# Acceleration_module.net
KiCad netlist of a schematic drawn in Altium Designer
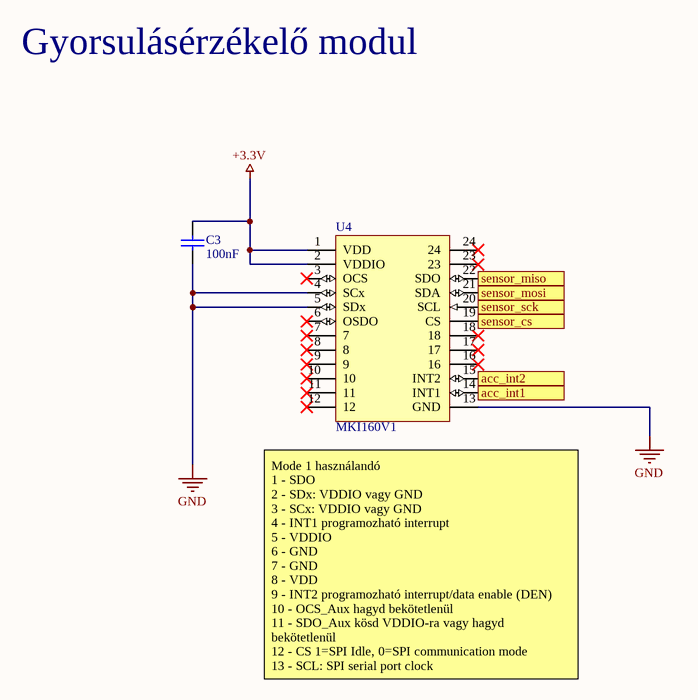
[diagram p0: Acceleration_module.SchDoc]

(export (version "E")
  (design (tool "Eeschema 10.0.6"))
  (components
    (comp (ref "C3")
      (value "100nF")
      (footprint "FP_1206_CAP_125")
      (description "Capacitor")
      (fields (field (name "TOLERANCE") "10%") (field (name "VOLTAGE") "50V"))
      (libsource (lib "hallglib") (part "CAP"))
    )
    (comp (ref "U4")
      (value "MKI160V1")
      (footprint "FP_DIL24")
      (description "LSM6DS3 inertial module adapter")
      (libsource (lib "hallglib") (part "MKI160V1"))
    )
  )
  (nets
    (net (code "1") (name "+3.3V") (class "Default")
      (node (ref "C3") (pin "2") (pinfunction "2_2") (pintype "passive"))
      (node (ref "U4") (pin "1") (pinfunction "VDD_1") (pintype "power_in"))
      (node (ref "U4") (pin "2") (pinfunction "VDDIO_2") (pintype "power_in"))
    )
    (net (code "2") (name "/acc_int1") (class "Default")
      (node (ref "U4") (pin "14") (pinfunction "INT1_14") (pintype "bidirectional"))
    )
    (net (code "3") (name "/acc_int2") (class "Default")
      (node (ref "U4") (pin "15") (pinfunction "INT2_15") (pintype "bidirectional"))
    )
    (net (code "4") (name "/sensor_cs") (class "Default")
      (node (ref "U4") (pin "19") (pinfunction "CS_19") (pintype "passive"))
    )
    (net (code "5") (name "/sensor_miso") (class "Default")
      (node (ref "U4") (pin "22") (pinfunction "SDO_22") (pintype "bidirectional"))
    )
    (net (code "6") (name "/sensor_mosi") (class "Default")
      (node (ref "U4") (pin "21") (pinfunction "SDA_21") (pintype "bidirectional"))
    )
    (net (code "7") (name "/sensor_sck") (class "Default")
      (node (ref "U4") (pin "20") (pinfunction "SCL_20") (pintype "input"))
    )
    (net (code "8") (name "GND") (class "Default")
      (node (ref "C3") (pin "1") (pinfunction "1_1") (pintype "passive"))
      (node (ref "U4") (pin "13") (pinfunction "GND_13") (pintype "power_in"))
      (node (ref "U4") (pin "4") (pinfunction "SCx_4") (pintype "bidirectional"))
      (node (ref "U4") (pin "5") (pinfunction "SDx_5") (pintype "bidirectional"))
    )
    (net (code "9") (name "unconnected-(U4-OCS-Pad3)") (class "Default")
      (node (ref "U4") (pin "3") (pinfunction "OCS_3") (pintype "bidirectional+no_connect"))
    )
    (net (code "10") (name "unconnected-(U4-OSDO-Pad6)") (class "Default")
      (node (ref "U4") (pin "6") (pinfunction "OSDO_6") (pintype "bidirectional+no_connect"))
    )
    (net (code "11") (name "unconnected-(U4-Pad7)") (class "Default")
      (node (ref "U4") (pin "7") (pinfunction "7_7") (pintype "passive+no_connect"))
    )
    (net (code "12") (name "unconnected-(U4-Pad8)") (class "Default")
      (node (ref "U4") (pin "8") (pinfunction "8_8") (pintype "passive+no_connect"))
    )
    (net (code "13") (name "unconnected-(U4-Pad9)") (class "Default")
      (node (ref "U4") (pin "9") (pinfunction "9_9") (pintype "passive+no_connect"))
    )
    (net (code "14") (name "unconnected-(U4-Pad10)") (class "Default")
      (node (ref "U4") (pin "10") (pinfunction "10_10") (pintype "passive+no_connect"))
    )
    (net (code "15") (name "unconnected-(U4-Pad11)") (class "Default")
      (node (ref "U4") (pin "11") (pinfunction "11_11") (pintype "passive+no_connect"))
    )
    (net (code "16") (name "unconnected-(U4-Pad12)") (class "Default")
      (node (ref "U4") (pin "12") (pinfunction "12_12") (pintype "passive+no_connect"))
    )
    (net (code "17") (name "unconnected-(U4-Pad16)") (class "Default")
      (node (ref "U4") (pin "16") (pinfunction "16_16") (pintype "passive+no_connect"))
    )
    (net (code "18") (name "unconnected-(U4-Pad17)") (class "Default")
      (node (ref "U4") (pin "17") (pinfunction "17_17") (pintype "passive+no_connect"))
    )
    (net (code "19") (name "unconnected-(U4-Pad18)") (class "Default")
      (node (ref "U4") (pin "18") (pinfunction "18_18") (pintype "passive+no_connect"))
    )
    (net (code "20") (name "unconnected-(U4-Pad23)") (class "Default")
      (node (ref "U4") (pin "23") (pinfunction "23_23") (pintype "passive+no_connect"))
    )
    (net (code "21") (name "unconnected-(U4-Pad24)") (class "Default")
      (node (ref "U4") (pin "24") (pinfunction "24_24") (pintype "passive+no_connect"))
    )
  )
)
